# stop_sign.net
KiCad netlist of a schematic drawn in Altium Designer
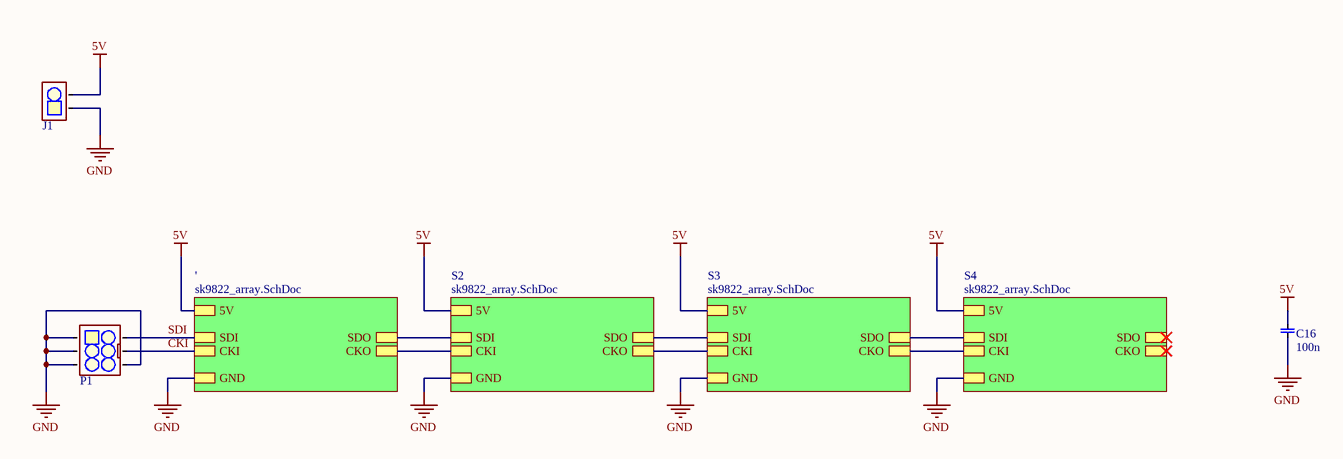
[diagram p0: stop_sign.SchDoc]

(export (version "E")
  (design (tool "Eeschema 10.0.6"))
  (components
    (comp (ref "C16")
      (value "100n")
      (footprint "0603 cap")
      (fields (field (name "Comment") "0603, capacitor"))
      (libsource (lib "sign_lib") (part "0603, capacitor"))
    )
    (comp (ref "J1")
      (value "2 Pole MSTBA Connector")
      (footprint "2POLE_MSTBA")
      (libsource (lib "sign_lib") (part "2 Pole MSTBA Connector"))
    )
    (comp (ref "P1")
      (value "2x3 Pin Header")
      (footprint "2x3 PH")
      (description "2x3 Ribbon connector")
      (libsource (lib "sign_lib") (part "2x3 Ribbon connector"))
    )
  )
  (nets
    (net (code "1") (name "/CKI") (class "Default")
      (node (ref "P1") (pin "5") (pinfunction "5_5") (pintype "passive"))
    )
    (net (code "6") (name "/SDI") (class "Default")
      (node (ref "P1") (pin "6") (pinfunction "6_6") (pintype "passive"))
    )
    (net (code "11") (name "5V") (class "Default")
      (node (ref "C16") (pin "1") (pinfunction "1_1") (pintype "passive"))
      (node (ref "J1") (pin "2") (pinfunction "2_2") (pintype "passive"))
    )
    (net (code "12") (name "GND") (class "Default")
      (node (ref "C16") (pin "0") (pinfunction "0_0") (pintype "passive"))
      (node (ref "J1") (pin "1") (pinfunction "1_1") (pintype "passive"))
      (node (ref "P1") (pin "1") (pinfunction "1_1") (pintype "passive"))
      (node (ref "P1") (pin "2") (pinfunction "2_2") (pintype "passive"))
      (node (ref "P1") (pin "3") (pinfunction "3_3") (pintype "passive"))
      (node (ref "P1") (pin "4") (pinfunction "4_4") (pintype "passive"))
    )
  )
)
